# Mechalino_Second_Layer.net
KiCad netlist of a schematic drawn in Altium Designer
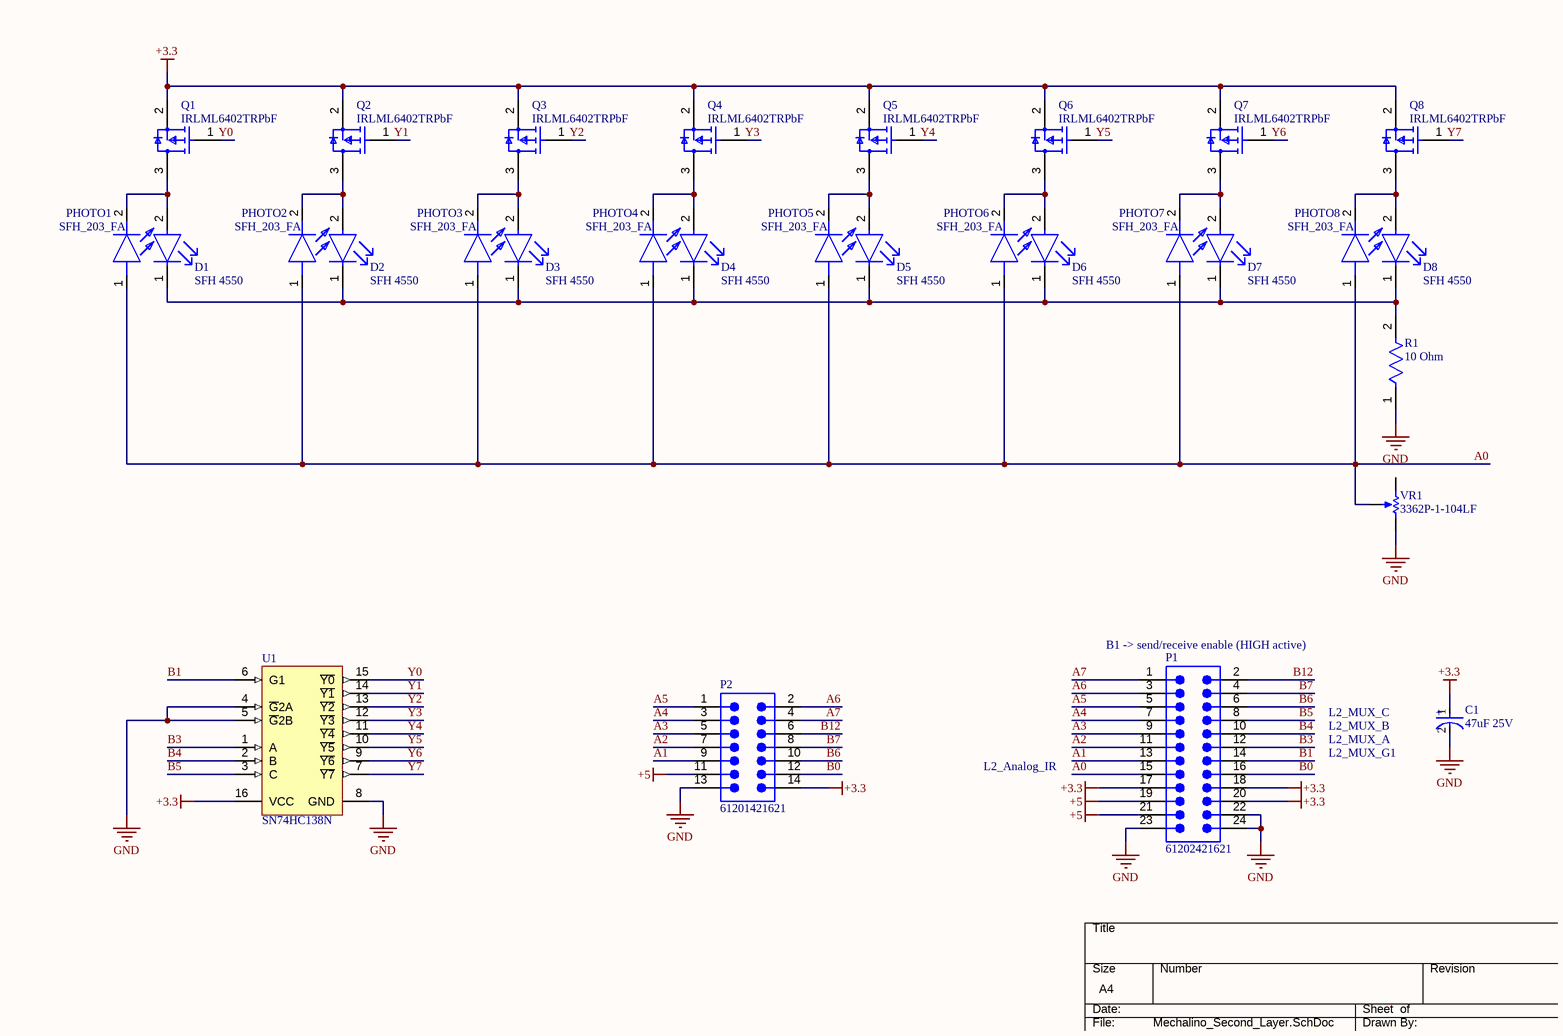
[diagram p0: Mechalino_Second_Layer.SchDoc]

(export (version "E")
  (design (tool "Eeschema 10.0.6"))
  (components
    (comp (ref "C1")
      (value "47uF 25V")
      (footprint "FP-FKD-MFG")
      (description "CAP ALUM 47UF 20% 25V SMD")
      (fields (field (name "TOLERANCE") "20%") (field (name "VOLTAGE") "25V"))
      (libsource (lib "Altium Content Vault") (part "af6b09250824f1546b97fbd1c504875"))
    )
    (comp (ref "D1")
      (value "SFH 4550")
      (footprint "FP-SFH_4550-MFG")
      (description "EMITTER IR 860NM 100MA RADIAL")
      (fields
        (field (name "OCTOPART") "https://octopart.com/sfh+4550-osram+opto-55410894")
        (field (name "MANUFACTURER") "Osram Opto")
      )
      (libsource (lib "Altium Content Vault") (part "75a0115997dd6a71327e26aab64f6f8"))
    )
    (comp (ref "D2")
      (value "SFH 4550")
      (footprint "FP-SFH_4550-MFG")
      (description "EMITTER IR 860NM 100MA RADIAL")
      (fields
        (field (name "OCTOPART") "https://octopart.com/sfh+4550-osram+opto-55410894")
        (field (name "MANUFACTURER") "Osram Opto")
      )
      (libsource (lib "Altium Content Vault") (part "75a0115997dd6a71327e26aab64f6f8"))
    )
    (comp (ref "D3")
      (value "SFH 4550")
      (footprint "FP-SFH_4550-MFG")
      (description "EMITTER IR 860NM 100MA RADIAL")
      (fields
        (field (name "OCTOPART") "https://octopart.com/sfh+4550-osram+opto-55410894")
        (field (name "MANUFACTURER") "Osram Opto")
      )
      (libsource (lib "Altium Content Vault") (part "75a0115997dd6a71327e26aab64f6f8"))
    )
    (comp (ref "D4")
      (value "SFH 4550")
      (footprint "FP-SFH_4550-MFG")
      (description "EMITTER IR 860NM 100MA RADIAL")
      (fields
        (field (name "OCTOPART") "https://octopart.com/sfh+4550-osram+opto-55410894")
        (field (name "MANUFACTURER") "Osram Opto")
      )
      (libsource (lib "Altium Content Vault") (part "75a0115997dd6a71327e26aab64f6f8"))
    )
    (comp (ref "D5")
      (value "SFH 4550")
      (footprint "FP-SFH_4550-MFG")
      (description "EMITTER IR 860NM 100MA RADIAL")
      (fields
        (field (name "OCTOPART") "https://octopart.com/sfh+4550-osram+opto-55410894")
        (field (name "MANUFACTURER") "Osram Opto")
      )
      (libsource (lib "Altium Content Vault") (part "75a0115997dd6a71327e26aab64f6f8"))
    )
    (comp (ref "D6")
      (value "SFH 4550")
      (footprint "FP-SFH_4550-MFG")
      (description "EMITTER IR 860NM 100MA RADIAL")
      (fields
        (field (name "OCTOPART") "https://octopart.com/sfh+4550-osram+opto-55410894")
        (field (name "MANUFACTURER") "Osram Opto")
      )
      (libsource (lib "Altium Content Vault") (part "75a0115997dd6a71327e26aab64f6f8"))
    )
    (comp (ref "D7")
      (value "SFH 4550")
      (footprint "FP-SFH_4550-MFG")
      (description "EMITTER IR 860NM 100MA RADIAL")
      (fields
        (field (name "OCTOPART") "https://octopart.com/sfh+4550-osram+opto-55410894")
        (field (name "MANUFACTURER") "Osram Opto")
      )
      (libsource (lib "Altium Content Vault") (part "75a0115997dd6a71327e26aab64f6f8"))
    )
    (comp (ref "D8")
      (value "SFH 4550")
      (footprint "FP-SFH_4550-MFG")
      (description "EMITTER IR 860NM 100MA RADIAL")
      (fields
        (field (name "OCTOPART") "https://octopart.com/sfh+4550-osram+opto-55410894")
        (field (name "MANUFACTURER") "Osram Opto")
      )
      (libsource (lib "Altium Content Vault") (part "75a0115997dd6a71327e26aab64f6f8"))
    )
    (comp (ref "P1")
      (value "61202421621")
      (footprint "61202421621")
      (libsource (lib "Altium Content Vault") (part "Header_Male_2R_24P"))
    )
    (comp (ref "P2")
      (value "61201421621")
      (footprint "61201421621")
      (libsource (lib "Altium Content Vault") (part "Header_Male_2R_14P"))
    )
    (comp (ref "PHOTO1")
      (value "SFH_203_FA")
      (footprint "SamacSys:SFH203FA")
      (description "PHOTO")
      (fields
        (field (name "MANUFACTURER_PART_NUMBER") "SFH 203 FA")
        (field (name "MOUSER PART NUMBER") "720-SFH203FA")
      )
      (libsource (lib "*") (part "SFH_203_FA"))
    )
    (comp (ref "PHOTO2")
      (value "SFH_203_FA")
      (footprint "SamacSys:SFH203FA")
      (description "PHOTO")
      (fields
        (field (name "MANUFACTURER_PART_NUMBER") "SFH 203 FA")
        (field (name "MOUSER PART NUMBER") "720-SFH203FA")
      )
      (libsource (lib "*") (part "SFH_203_FA"))
    )
    (comp (ref "PHOTO3")
      (value "SFH_203_FA")
      (footprint "SamacSys:SFH203FA")
      (description "PHOTO")
      (fields
        (field (name "MANUFACTURER_PART_NUMBER") "SFH 203 FA")
        (field (name "MOUSER PART NUMBER") "720-SFH203FA")
      )
      (libsource (lib "*") (part "SFH_203_FA"))
    )
    (comp (ref "PHOTO4")
      (value "SFH_203_FA")
      (footprint "SamacSys:SFH203FA")
      (description "PHOTO")
      (fields
        (field (name "MANUFACTURER_PART_NUMBER") "SFH 203 FA")
        (field (name "MOUSER PART NUMBER") "720-SFH203FA")
      )
      (libsource (lib "*") (part "SFH_203_FA"))
    )
    (comp (ref "PHOTO5")
      (value "SFH_203_FA")
      (footprint "SamacSys:SFH203FA")
      (description "PHOTO")
      (fields
        (field (name "MANUFACTURER_PART_NUMBER") "SFH 203 FA")
        (field (name "MOUSER PART NUMBER") "720-SFH203FA")
      )
      (libsource (lib "*") (part "SFH_203_FA"))
    )
    (comp (ref "PHOTO6")
      (value "SFH_203_FA")
      (footprint "SamacSys:SFH203FA")
      (description "PHOTO")
      (fields
        (field (name "MANUFACTURER_PART_NUMBER") "SFH 203 FA")
        (field (name "MOUSER PART NUMBER") "720-SFH203FA")
      )
      (libsource (lib "*") (part "SFH_203_FA"))
    )
    (comp (ref "PHOTO7")
      (value "SFH_203_FA")
      (footprint "SamacSys:SFH203FA")
      (description "PHOTO")
      (fields
        (field (name "MANUFACTURER_PART_NUMBER") "SFH 203 FA")
        (field (name "MOUSER PART NUMBER") "720-SFH203FA")
      )
      (libsource (lib "*") (part "SFH_203_FA"))
    )
    (comp (ref "PHOTO8")
      (value "SFH_203_FA")
      (footprint "SamacSys:SFH203FA")
      (description "PHOTO")
      (fields
        (field (name "MANUFACTURER_PART_NUMBER") "SFH 203 FA")
        (field (name "MOUSER PART NUMBER") "720-SFH203FA")
      )
      (libsource (lib "*") (part "SFH_203_FA"))
    )
    (comp (ref "Q1")
      (value "IRLML6402TRPbF")
      (footprint "FP-Micro3-MFG")
      (description "MOSFET P-CH 20V 3.7A SOT-23")
      (fields
        (field (name "OCTOPART") "https://octopart.com/irlml6402trpbf-infineon-65874989")
        (field (name "MANUFACTURER PART NUMBER") "IRLML6402TRPBF")
      )
      (libsource (lib "Altium Content Vault") (part "566027c8dc92b5207d53ac25ab3eb60"))
    )
    (comp (ref "Q2")
      (value "IRLML6402TRPbF")
      (footprint "FP-Micro3-MFG")
      (description "MOSFET P-CH 20V 3.7A SOT-23")
      (fields
        (field (name "OCTOPART") "https://octopart.com/irlml6402trpbf-infineon-65874989")
        (field (name "MANUFACTURER PART NUMBER") "IRLML6402TRPBF")
      )
      (libsource (lib "Altium Content Vault") (part "566027c8dc92b5207d53ac25ab3eb60"))
    )
    (comp (ref "Q3")
      (value "IRLML6402TRPbF")
      (footprint "FP-Micro3-MFG")
      (description "MOSFET P-CH 20V 3.7A SOT-23")
      (fields
        (field (name "OCTOPART") "https://octopart.com/irlml6402trpbf-infineon-65874989")
        (field (name "MANUFACTURER PART NUMBER") "IRLML6402TRPBF")
      )
      (libsource (lib "Altium Content Vault") (part "566027c8dc92b5207d53ac25ab3eb60"))
    )
    (comp (ref "Q4")
      (value "IRLML6402TRPbF")
      (footprint "FP-Micro3-MFG")
      (description "MOSFET P-CH 20V 3.7A SOT-23")
      (fields
        (field (name "OCTOPART") "https://octopart.com/irlml6402trpbf-infineon-65874989")
        (field (name "MANUFACTURER PART NUMBER") "IRLML6402TRPBF")
      )
      (libsource (lib "Altium Content Vault") (part "566027c8dc92b5207d53ac25ab3eb60"))
    )
    (comp (ref "Q5")
      (value "IRLML6402TRPbF")
      (footprint "FP-Micro3-MFG")
      (description "MOSFET P-CH 20V 3.7A SOT-23")
      (fields
        (field (name "OCTOPART") "https://octopart.com/irlml6402trpbf-infineon-65874989")
        (field (name "MANUFACTURER PART NUMBER") "IRLML6402TRPBF")
      )
      (libsource (lib "Altium Content Vault") (part "566027c8dc92b5207d53ac25ab3eb60"))
    )
    (comp (ref "Q6")
      (value "IRLML6402TRPbF")
      (footprint "FP-Micro3-MFG")
      (description "MOSFET P-CH 20V 3.7A SOT-23")
      (fields
        (field (name "OCTOPART") "https://octopart.com/irlml6402trpbf-infineon-65874989")
        (field (name "MANUFACTURER PART NUMBER") "IRLML6402TRPBF")
      )
      (libsource (lib "Altium Content Vault") (part "566027c8dc92b5207d53ac25ab3eb60"))
    )
    (comp (ref "Q7")
      (value "IRLML6402TRPbF")
      (footprint "FP-Micro3-MFG")
      (description "MOSFET P-CH 20V 3.7A SOT-23")
      (fields
        (field (name "OCTOPART") "https://octopart.com/irlml6402trpbf-infineon-65874989")
        (field (name "MANUFACTURER PART NUMBER") "IRLML6402TRPBF")
      )
      (libsource (lib "Altium Content Vault") (part "566027c8dc92b5207d53ac25ab3eb60"))
    )
    (comp (ref "Q8")
      (value "IRLML6402TRPbF")
      (footprint "FP-Micro3-MFG")
      (description "MOSFET P-CH 20V 3.7A SOT-23")
      (fields
        (field (name "OCTOPART") "https://octopart.com/irlml6402trpbf-infineon-65874989")
        (field (name "MANUFACTURER PART NUMBER") "IRLML6402TRPBF")
      )
      (libsource (lib "Altium Content Vault") (part "566027c8dc92b5207d53ac25ab3eb60"))
    )
    (comp (ref "R1")
      (value "10 Ohm")
      (footprint "FP-ESR25-IPC_B")
      (description "10Ω ±5% 0.66W 1210 Anti-Surge Chip Resistor AEC-Q200")
      (fields (field (name "TOLERANCE") "5%"))
      (libsource (lib "Altium Content Vault") (part "1029c3af85768c4190bb7ad29bc67b5"))
    )
    (comp (ref "U1")
      (value "SN74HC138N")
      (footprint "N0016A")
      (description "3-Line To 8-Line Decoders/Demultiplexers, N0016A, TUBE")
      (fields
        (field (name "MANUFACTURER") "Texas Instruments")
        (field (name "GENERIC PART NUMBER") "SN74HC138")
      )
      (libsource (lib "Altium Content Vault") (part "TI-SNX4XXXX138-16"))
    )
    (comp (ref "VR1")
      (value "3362P-1-104LF")
      (footprint "BOUR-3362P")
      (description "Square Trimpot(R) Trimming Potentiometer, 100 KOhm, 300 V, -55 to 125 degC, 3-Pin THD, RoHS, Tube")
      (fields (field (name "TOLERANCE") "1%"))
      (libsource (lib "Altium Content Vault") (part "RES-POT-3"))
    )
  )
  (nets
    (net (code "1") (name "+3.3") (class "Default")
      (node (ref "C1") (pin "1") (pinfunction "C_1") (pintype "passive"))
      (node (ref "P1") (pin "17") (pinfunction "17_17") (pintype "passive"))
      (node (ref "P1") (pin "18") (pinfunction "18_18") (pintype "passive"))
      (node (ref "P1") (pin "20") (pinfunction "20_20") (pintype "passive"))
      (node (ref "P2") (pin "14") (pinfunction "14_14") (pintype "passive"))
      (node (ref "Q1") (pin "2") (pinfunction "S_2") (pintype "passive"))
      (node (ref "Q2") (pin "2") (pinfunction "S_2") (pintype "passive"))
      (node (ref "Q3") (pin "2") (pinfunction "S_2") (pintype "passive"))
      (node (ref "Q4") (pin "2") (pinfunction "S_2") (pintype "passive"))
      (node (ref "Q5") (pin "2") (pinfunction "S_2") (pintype "passive"))
      (node (ref "Q6") (pin "2") (pinfunction "S_2") (pintype "passive"))
      (node (ref "Q7") (pin "2") (pinfunction "S_2") (pintype "passive"))
      (node (ref "Q8") (pin "2") (pinfunction "S_2") (pintype "passive"))
      (node (ref "U1") (pin "16") (pinfunction "VCC_16") (pintype "power_in"))
    )
    (net (code "2") (name "+5") (class "Default")
      (node (ref "P1") (pin "19") (pinfunction "19_19") (pintype "passive"))
      (node (ref "P1") (pin "21") (pinfunction "21_21") (pintype "passive"))
      (node (ref "P2") (pin "11") (pinfunction "11_11") (pintype "passive"))
    )
    (net (code "3") (name "/A0") (class "Default")
      (node (ref "P1") (pin "15") (pinfunction "15_15") (pintype "passive"))
      (node (ref "PHOTO1") (pin "1") (pinfunction "A_1") (pintype "passive"))
      (node (ref "PHOTO2") (pin "1") (pinfunction "A_1") (pintype "passive"))
      (node (ref "PHOTO3") (pin "1") (pinfunction "A_1") (pintype "passive"))
      (node (ref "PHOTO4") (pin "1") (pinfunction "A_1") (pintype "passive"))
      (node (ref "PHOTO5") (pin "1") (pinfunction "A_1") (pintype "passive"))
      (node (ref "PHOTO6") (pin "1") (pinfunction "A_1") (pintype "passive"))
      (node (ref "PHOTO7") (pin "1") (pinfunction "A_1") (pintype "passive"))
      (node (ref "PHOTO8") (pin "1") (pinfunction "A_1") (pintype "passive"))
      (node (ref "VR1") (pin "2") (pinfunction "S_2") (pintype "passive"))
    )
    (net (code "4") (name "/A1") (class "Default")
      (node (ref "P1") (pin "13") (pinfunction "13_13") (pintype "passive"))
      (node (ref "P2") (pin "9") (pinfunction "9_9") (pintype "passive"))
    )
    (net (code "5") (name "/A2") (class "Default")
      (node (ref "P1") (pin "11") (pinfunction "11_11") (pintype "passive"))
      (node (ref "P2") (pin "7") (pinfunction "7_7") (pintype "passive"))
    )
    (net (code "6") (name "/A3") (class "Default")
      (node (ref "P1") (pin "9") (pinfunction "9_9") (pintype "passive"))
      (node (ref "P2") (pin "5") (pinfunction "5_5") (pintype "passive"))
    )
    (net (code "7") (name "/A4") (class "Default")
      (node (ref "P1") (pin "7") (pinfunction "7_7") (pintype "passive"))
      (node (ref "P2") (pin "3") (pinfunction "3_3") (pintype "passive"))
    )
    (net (code "8") (name "/A5") (class "Default")
      (node (ref "P1") (pin "5") (pinfunction "5_5") (pintype "passive"))
      (node (ref "P2") (pin "1") (pinfunction "1_1") (pintype "passive"))
    )
    (net (code "9") (name "/A6") (class "Default")
      (node (ref "P1") (pin "3") (pinfunction "3_3") (pintype "passive"))
      (node (ref "P2") (pin "2") (pinfunction "2_2") (pintype "passive"))
    )
    (net (code "10") (name "/A7") (class "Default")
      (node (ref "P1") (pin "1") (pinfunction "1_1") (pintype "passive"))
      (node (ref "P2") (pin "4") (pinfunction "4_4") (pintype "passive"))
    )
    (net (code "11") (name "/B0") (class "Default")
      (node (ref "P1") (pin "16") (pinfunction "16_16") (pintype "passive"))
      (node (ref "P2") (pin "12") (pinfunction "12_12") (pintype "passive"))
    )
    (net (code "12") (name "/B1") (class "Default")
      (node (ref "P1") (pin "14") (pinfunction "14_14") (pintype "passive"))
      (node (ref "U1") (pin "6") (pinfunction "G1_6") (pintype "input"))
    )
    (net (code "13") (name "/B3") (class "Default")
      (node (ref "P1") (pin "12") (pinfunction "12_12") (pintype "passive"))
      (node (ref "U1") (pin "1") (pinfunction "A_1") (pintype "input"))
    )
    (net (code "14") (name "/B4") (class "Default")
      (node (ref "P1") (pin "10") (pinfunction "10_10") (pintype "passive"))
      (node (ref "U1") (pin "2") (pinfunction "B_2") (pintype "input"))
    )
    (net (code "15") (name "/B5") (class "Default")
      (node (ref "P1") (pin "8") (pinfunction "8_8") (pintype "passive"))
      (node (ref "U1") (pin "3") (pinfunction "C_3") (pintype "input"))
    )
    (net (code "16") (name "/B6") (class "Default")
      (node (ref "P1") (pin "6") (pinfunction "6_6") (pintype "passive"))
      (node (ref "P2") (pin "10") (pinfunction "10_10") (pintype "passive"))
    )
    (net (code "17") (name "/B7") (class "Default")
      (node (ref "P1") (pin "4") (pinfunction "4_4") (pintype "passive"))
      (node (ref "P2") (pin "8") (pinfunction "8_8") (pintype "passive"))
    )
    (net (code "18") (name "/B12") (class "Default")
      (node (ref "P1") (pin "2") (pinfunction "2_2") (pintype "passive"))
      (node (ref "P2") (pin "6") (pinfunction "6_6") (pintype "passive"))
    )
    (net (code "19") (name "/Y0") (class "Default")
      (node (ref "Q1") (pin "1") (pinfunction "G_1") (pintype "passive"))
      (node (ref "U1") (pin "15") (pinfunction "~{Y0}_15") (pintype "output"))
    )
    (net (code "20") (name "/Y1") (class "Default")
      (node (ref "Q2") (pin "1") (pinfunction "G_1") (pintype "passive"))
      (node (ref "U1") (pin "14") (pinfunction "~{Y1}_14") (pintype "output"))
    )
    (net (code "21") (name "/Y2") (class "Default")
      (node (ref "Q3") (pin "1") (pinfunction "G_1") (pintype "passive"))
      (node (ref "U1") (pin "13") (pinfunction "~{Y2}_13") (pintype "output"))
    )
    (net (code "22") (name "/Y3") (class "Default")
      (node (ref "Q4") (pin "1") (pinfunction "G_1") (pintype "passive"))
      (node (ref "U1") (pin "12") (pinfunction "~{Y3}_12") (pintype "output"))
    )
    (net (code "23") (name "/Y4") (class "Default")
      (node (ref "Q5") (pin "1") (pinfunction "G_1") (pintype "passive"))
      (node (ref "U1") (pin "11") (pinfunction "~{Y4}_11") (pintype "output"))
    )
    (net (code "24") (name "/Y5") (class "Default")
      (node (ref "Q6") (pin "1") (pinfunction "G_1") (pintype "passive"))
      (node (ref "U1") (pin "10") (pinfunction "~{Y5}_10") (pintype "output"))
    )
    (net (code "25") (name "/Y6") (class "Default")
      (node (ref "Q7") (pin "1") (pinfunction "G_1") (pintype "passive"))
      (node (ref "U1") (pin "9") (pinfunction "~{Y6}_9") (pintype "output"))
    )
    (net (code "26") (name "/Y7") (class "Default")
      (node (ref "Q8") (pin "1") (pinfunction "G_1") (pintype "passive"))
      (node (ref "U1") (pin "7") (pinfunction "~{Y7}_7") (pintype "output"))
    )
    (net (code "27") (name "GND") (class "Default")
      (node (ref "C1") (pin "2") (pinfunction "A_2") (pintype "passive"))
      (node (ref "P1") (pin "22") (pinfunction "22_22") (pintype "passive"))
      (node (ref "P1") (pin "23") (pinfunction "23_23") (pintype "passive"))
      (node (ref "P1") (pin "24") (pinfunction "24_24") (pintype "passive"))
      (node (ref "P2") (pin "13") (pinfunction "13_13") (pintype "passive"))
      (node (ref "R1") (pin "1") (pinfunction "1_1") (pintype "passive"))
      (node (ref "U1") (pin "4") (pinfunction "~{G}2A_4") (pintype "input"))
      (node (ref "U1") (pin "5") (pinfunction "~{G}2B_5") (pintype "input"))
      (node (ref "U1") (pin "8") (pinfunction "GND_8") (pintype "power_in"))
      (node (ref "VR1") (pin "3") (pinfunction "CW_3") (pintype "passive"))
    )
    (net (code "28") (name "Net-(D1-A)") (class "Default")
      (node (ref "D1") (pin "2") (pinfunction "A_2") (pintype "passive"))
      (node (ref "PHOTO1") (pin "2") (pinfunction "K_2") (pintype "passive"))
      (node (ref "Q1") (pin "3") (pinfunction "D_3") (pintype "passive"))
    )
    (net (code "29") (name "Net-(D1-C)") (class "Default")
      (node (ref "D1") (pin "1") (pinfunction "C_1") (pintype "passive"))
      (node (ref "D2") (pin "1") (pinfunction "C_1") (pintype "passive"))
      (node (ref "D3") (pin "1") (pinfunction "C_1") (pintype "passive"))
      (node (ref "D4") (pin "1") (pinfunction "C_1") (pintype "passive"))
      (node (ref "D5") (pin "1") (pinfunction "C_1") (pintype "passive"))
      (node (ref "D6") (pin "1") (pinfunction "C_1") (pintype "passive"))
      (node (ref "D7") (pin "1") (pinfunction "C_1") (pintype "passive"))
      (node (ref "D8") (pin "1") (pinfunction "C_1") (pintype "passive"))
      (node (ref "R1") (pin "2") (pinfunction "2_2") (pintype "passive"))
    )
    (net (code "30") (name "Net-(D2-A)") (class "Default")
      (node (ref "D2") (pin "2") (pinfunction "A_2") (pintype "passive"))
      (node (ref "PHOTO2") (pin "2") (pinfunction "K_2") (pintype "passive"))
      (node (ref "Q2") (pin "3") (pinfunction "D_3") (pintype "passive"))
    )
    (net (code "31") (name "Net-(D3-A)") (class "Default")
      (node (ref "D3") (pin "2") (pinfunction "A_2") (pintype "passive"))
      (node (ref "PHOTO3") (pin "2") (pinfunction "K_2") (pintype "passive"))
      (node (ref "Q3") (pin "3") (pinfunction "D_3") (pintype "passive"))
    )
    (net (code "32") (name "Net-(D4-A)") (class "Default")
      (node (ref "D4") (pin "2") (pinfunction "A_2") (pintype "passive"))
      (node (ref "PHOTO4") (pin "2") (pinfunction "K_2") (pintype "passive"))
      (node (ref "Q4") (pin "3") (pinfunction "D_3") (pintype "passive"))
    )
    (net (code "33") (name "Net-(D5-A)") (class "Default")
      (node (ref "D5") (pin "2") (pinfunction "A_2") (pintype "passive"))
      (node (ref "PHOTO5") (pin "2") (pinfunction "K_2") (pintype "passive"))
      (node (ref "Q5") (pin "3") (pinfunction "D_3") (pintype "passive"))
    )
    (net (code "34") (name "Net-(D6-A)") (class "Default")
      (node (ref "D6") (pin "2") (pinfunction "A_2") (pintype "passive"))
      (node (ref "PHOTO6") (pin "2") (pinfunction "K_2") (pintype "passive"))
      (node (ref "Q6") (pin "3") (pinfunction "D_3") (pintype "passive"))
    )
    (net (code "35") (name "Net-(D7-A)") (class "Default")
      (node (ref "D7") (pin "2") (pinfunction "A_2") (pintype "passive"))
      (node (ref "PHOTO7") (pin "2") (pinfunction "K_2") (pintype "passive"))
      (node (ref "Q7") (pin "3") (pinfunction "D_3") (pintype "passive"))
    )
    (net (code "36") (name "Net-(D8-A)") (class "Default")
      (node (ref "D8") (pin "2") (pinfunction "A_2") (pintype "passive"))
      (node (ref "PHOTO8") (pin "2") (pinfunction "K_2") (pintype "passive"))
      (node (ref "Q8") (pin "3") (pinfunction "D_3") (pintype "passive"))
    )
    (net (code "37") (name "unconnected-(VR1-CCW-Pad1)") (class "Default")
      (node (ref "VR1") (pin "1") (pinfunction "CCW_1") (pintype "passive"))
    )
  )
)
